# 02_MCU.net
KiCad netlist of a schematic drawn in Altium Designer
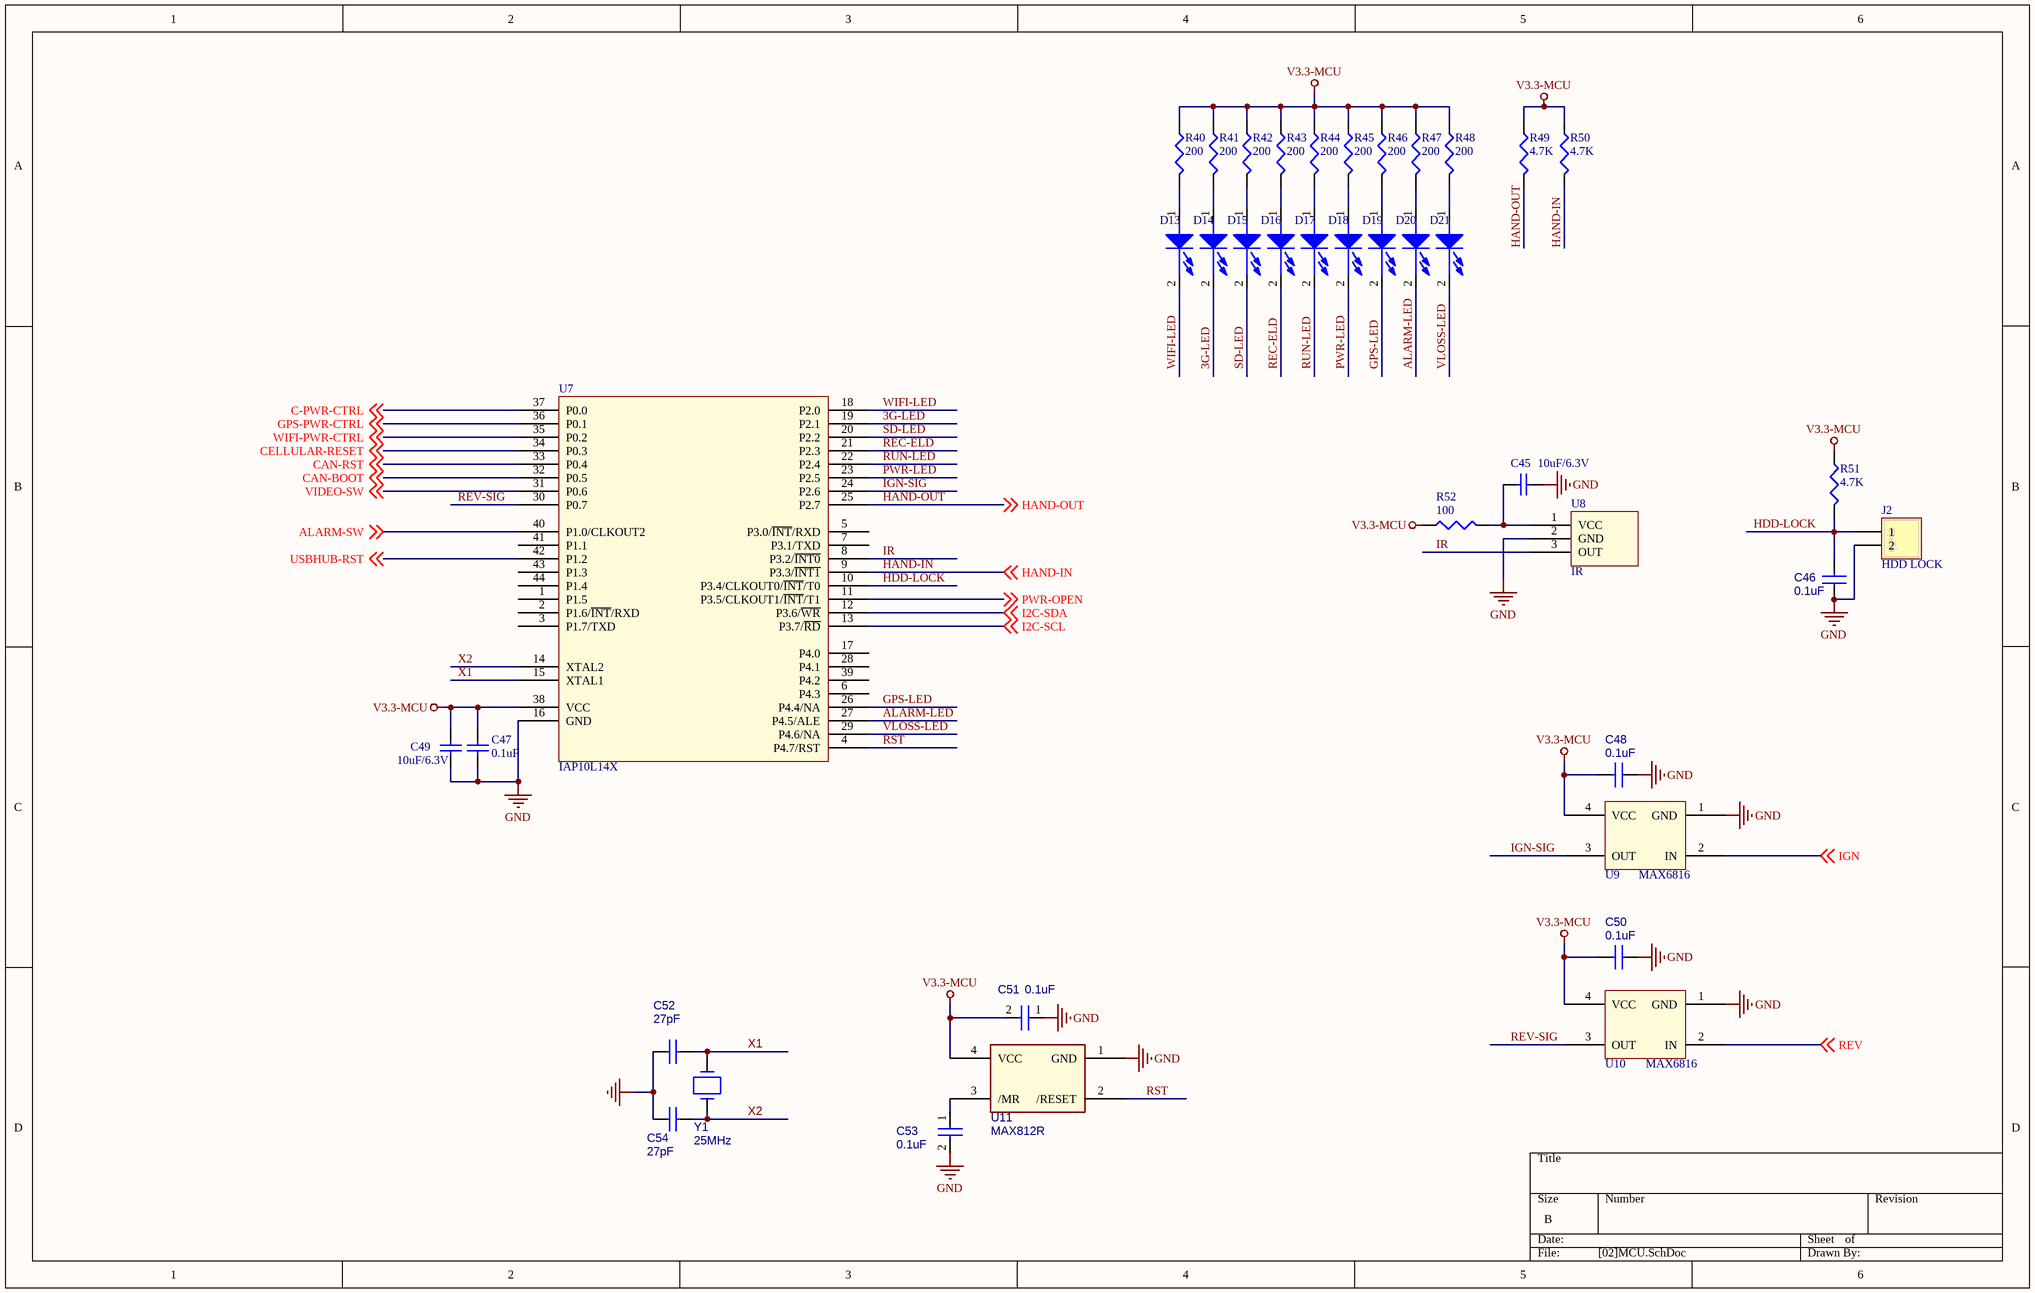
[diagram p0: [02]MCU.SchDoc]

(export (version "E")
  (design (tool "Eeschema 10.0.6"))
  (components
    (comp (ref "C45")
      (value "10uF/6.3V")
      (footprint "0805")
      (description "Capacitor")
      (libsource (lib "Miscellaneous Devices") (part "Cap"))
    )
    (comp (ref "C46") (value "0.1uF") (libsource (lib "*") (part "CAP")))
    (comp (ref "C47")
      (value "0.1uF")
      (footprint "0603")
      (description "Capacitor")
      (libsource (lib "Miscellaneous Devices") (part "Cap"))
    )
    (comp (ref "C48") (value "0.1uF") (libsource (lib "*") (part "CAP")))
    (comp (ref "C49")
      (value "10uF/6.3V")
      (footprint "0805")
      (description "Capacitor")
      (libsource (lib "Miscellaneous Devices") (part "Cap"))
    )
    (comp (ref "C50") (value "0.1uF") (libsource (lib "*") (part "CAP")))
    (comp (ref "C51") (value "0.1uF") (libsource (lib "*") (part "CAP NP_Dup2")))
    (comp (ref "C52") (value "27pF") (libsource (lib "*") (part "CAP_Dup1")))
    (comp (ref "C53") (value "0.1uF") (libsource (lib "*") (part "CAP NP_Dup2")))
    (comp (ref "C54") (value "27pF") (libsource (lib "*") (part "CAP_Dup1")))
    (comp (ref "D13") (value "LED GREEN") (footprint "LED-3MM") (libsource (lib "*") (part "LN01401_1")))
    (comp (ref "D14") (value "LED GREEN") (footprint "LED-3MM") (libsource (lib "*") (part "LN01401_1")))
    (comp (ref "D15") (value "LED GREEN") (footprint "LED-3MM") (libsource (lib "*") (part "LN01401_1")))
    (comp (ref "D16") (value "LED GREEN") (footprint "LED-3MM") (libsource (lib "*") (part "LN01401_1")))
    (comp (ref "D17") (value "LED GREEN") (footprint "LED-3MM") (libsource (lib "*") (part "LN01401_1")))
    (comp (ref "D18") (value "LED GREEN") (footprint "LED-3MM") (libsource (lib "*") (part "LN01401_1")))
    (comp (ref "D19") (value "LED GREEN") (footprint "LED-3MM") (libsource (lib "*") (part "LN01401_1")))
    (comp (ref "D20") (value "LED GREEN") (footprint "LED-3MM") (libsource (lib "*") (part "LN01401_1")))
    (comp (ref "D21") (value "LED GREEN") (footprint "LED-3MM") (libsource (lib "*") (part "LN01401_1")))
    (comp (ref "J2")
      (value "HDD LOCK")
      (footprint "CON-2PIN")
      (description "Header, 2-Pin")
      (fields (field (name "PUBLISHER") "Altium Limited"))
      (libsource (lib "Miscellaneous Connectors") (part "Header 2"))
    )
    (comp (ref "R40") (value "200") (footprint "0603") (libsource (lib "*") (part "CR16-1003FM")))
    (comp (ref "R41") (value "200") (footprint "0603") (libsource (lib "*") (part "CR16-1003FM")))
    (comp (ref "R42") (value "200") (footprint "0603") (libsource (lib "*") (part "CR16-1003FM")))
    (comp (ref "R43") (value "200") (footprint "0603") (libsource (lib "*") (part "CR16-1003FM")))
    (comp (ref "R44") (value "200") (footprint "0603") (libsource (lib "*") (part "CR16-1003FM")))
    (comp (ref "R45") (value "200") (footprint "0603") (libsource (lib "*") (part "CR16-1003FM")))
    (comp (ref "R46") (value "200") (footprint "0603") (libsource (lib "*") (part "CR16-1003FM")))
    (comp (ref "R47") (value "200") (footprint "0603") (libsource (lib "*") (part "CR16-1003FM")))
    (comp (ref "R48") (value "200") (footprint "0603") (libsource (lib "*") (part "CR16-1003FM")))
    (comp (ref "R49") (value "4.7K") (footprint "0603") (libsource (lib "*") (part "CR16-1003FM")))
    (comp (ref "R50") (value "4.7K") (footprint "0603") (libsource (lib "*") (part "CR16-1003FM")))
    (comp (ref "R51") (value "4.7K") (footprint "0603") (libsource (lib "*") (part "CR16-1003FM")))
    (comp (ref "R52") (value "100") (footprint "0603") (libsource (lib "*") (part "CR16-1003FM")))
    (comp (ref "U7") (value "IAP10L14X") (footprint "LQFP44") (libsource (lib "Schlib") (part "IAP10L14X")))
    (comp (ref "U8") (value "IR") (footprint "IR") (libsource (lib "Schlib") (part "IR")))
    (comp (ref "U9") (value "MAX6816") (footprint "SOT143") (libsource (lib "Schlib") (part "MAX6816")))
    (comp (ref "U10") (value "MAX6816") (footprint "SOT143") (libsource (lib "Schlib") (part "MAX6816")))
    (comp (ref "U11") (value "MAX812R") (libsource (lib "*") (part "MAX811")))
    (comp (ref "Y1") (value "25MHz") (libsource (lib "*") (part "CRYSTAL")))
  )
  (nets
    (net (code "1") (name "/3G-LED") (class "Default")
      (node (ref "D14") (pin "2") (pinfunction "CATHODE_2") (pintype "passive"))
      (node (ref "U7") (pin "19") (pinfunction "P2.1_19") (pintype "passive"))
    )
    (net (code "2") (name "/ALARM-LED") (class "Default")
      (node (ref "D20") (pin "2") (pinfunction "CATHODE_2") (pintype "passive"))
      (node (ref "U7") (pin "27") (pinfunction "P4.5/ALE_27") (pintype "passive"))
    )
    (net (code "3") (name "/GPS-LED") (class "Default")
      (node (ref "D19") (pin "2") (pinfunction "CATHODE_2") (pintype "passive"))
      (node (ref "U7") (pin "26") (pinfunction "P4.4/NA_26") (pintype "passive"))
    )
    (net (code "4") (name "/HDD-LOCK") (class "Default")
      (node (ref "C46") (pin "2") (pinfunction "2_2") (pintype "passive"))
      (node (ref "J2") (pin "1") (pinfunction "1_1") (pintype "passive"))
      (node (ref "R51") (pin "2") (pinfunction "2_2") (pintype "passive"))
      (node (ref "U7") (pin "10") (pinfunction "P3.4/CLKOUT0/~{INT}/T0_10") (pintype "passive"))
    )
    (net (code "5") (name "/IGN-SIG") (class "Default")
      (node (ref "U7") (pin "24") (pinfunction "P2.6_24") (pintype "passive"))
      (node (ref "U9") (pin "3") (pinfunction "OUT_3") (pintype "passive"))
    )
    (net (code "6") (name "/IR") (class "Default")
      (node (ref "U7") (pin "8") (pinfunction "P3.2/~{INT0}_8") (pintype "passive"))
      (node (ref "U8") (pin "3") (pinfunction "OUT_3") (pintype "passive"))
    )
    (net (code "7") (name "/PWR-LED") (class "Default")
      (node (ref "D18") (pin "2") (pinfunction "CATHODE_2") (pintype "passive"))
      (node (ref "U7") (pin "23") (pinfunction "P2.5_23") (pintype "passive"))
    )
    (net (code "8") (name "/REC-ELD") (class "Default")
      (node (ref "D16") (pin "2") (pinfunction "CATHODE_2") (pintype "passive"))
      (node (ref "U7") (pin "21") (pinfunction "P2.3_21") (pintype "passive"))
    )
    (net (code "9") (name "/REV-SIG") (class "Default")
      (node (ref "U10") (pin "3") (pinfunction "OUT_3") (pintype "passive"))
      (node (ref "U7") (pin "30") (pinfunction "P0.7_30") (pintype "passive"))
    )
    (net (code "10") (name "/RST") (class "Default")
      (node (ref "U11") (pin "2") (pinfunction "/RESET_2") (pintype "passive"))
      (node (ref "U7") (pin "4") (pinfunction "P4.7/RST_4") (pintype "passive"))
    )
    (net (code "11") (name "/RUN-LED") (class "Default")
      (node (ref "D17") (pin "2") (pinfunction "CATHODE_2") (pintype "passive"))
      (node (ref "U7") (pin "22") (pinfunction "P2.4_22") (pintype "passive"))
    )
    (net (code "12") (name "/SD-LED") (class "Default")
      (node (ref "D15") (pin "2") (pinfunction "CATHODE_2") (pintype "passive"))
      (node (ref "U7") (pin "20") (pinfunction "P2.2_20") (pintype "passive"))
    )
    (net (code "13") (name "/VLOSS-LED") (class "Default")
      (node (ref "D21") (pin "2") (pinfunction "CATHODE_2") (pintype "passive"))
      (node (ref "U7") (pin "29") (pinfunction "P4.6/NA_29") (pintype "passive"))
    )
    (net (code "14") (name "/WIFI-LED") (class "Default")
      (node (ref "D13") (pin "2") (pinfunction "CATHODE_2") (pintype "passive"))
      (node (ref "U7") (pin "18") (pinfunction "P2.0_18") (pintype "passive"))
    )
    (net (code "15") (name "/X1") (class "Default")
      (node (ref "C52") (pin "2") (pinfunction "2_2") (pintype "passive"))
      (node (ref "U7") (pin "15") (pinfunction "XTAL1_15") (pintype "passive"))
      (node (ref "Y1") (pin "2") (pinfunction "2_2") (pintype "passive"))
    )
    (net (code "16") (name "/X2") (class "Default")
      (node (ref "C54") (pin "2") (pinfunction "2_2") (pintype "passive"))
      (node (ref "U7") (pin "14") (pinfunction "XTAL2_14") (pintype "passive"))
      (node (ref "Y1") (pin "1") (pinfunction "1_1") (pintype "passive"))
    )
    (net (code "17") (name "ALARM-SW") (class "Default")
      (node (ref "U7") (pin "40") (pinfunction "P1.0/CLKOUT2_40") (pintype "passive"))
    )
    (net (code "18") (name "C-PWR-CTRL") (class "Default")
      (node (ref "U7") (pin "37") (pinfunction "P0.0_37") (pintype "passive"))
    )
    (net (code "19") (name "CAN-BOOT") (class "Default")
      (node (ref "U7") (pin "32") (pinfunction "P0.5_32") (pintype "passive"))
    )
    (net (code "20") (name "CAN-RST") (class "Default")
      (node (ref "U7") (pin "33") (pinfunction "P0.4_33") (pintype "passive"))
    )
    (net (code "21") (name "CELLULAR-RESET") (class "Default")
      (node (ref "U7") (pin "34") (pinfunction "P0.3_34") (pintype "passive"))
    )
    (net (code "22") (name "GND") (class "Default")
      (node (ref "C45") (pin "1") (pinfunction "1_1") (pintype "passive"))
      (node (ref "C46") (pin "1") (pinfunction "1_1") (pintype "passive"))
      (node (ref "C47") (pin "1") (pinfunction "1_1") (pintype "passive"))
      (node (ref "C48") (pin "1") (pinfunction "1_1") (pintype "passive"))
      (node (ref "C49") (pin "1") (pinfunction "1_1") (pintype "passive"))
      (node (ref "C50") (pin "1") (pinfunction "1_1") (pintype "passive"))
      (node (ref "C51") (pin "1") (pinfunction "1_1") (pintype "passive"))
      (node (ref "C52") (pin "1") (pinfunction "1_1") (pintype "passive"))
      (node (ref "C53") (pin "2") (pinfunction "2_2") (pintype "passive"))
      (node (ref "C54") (pin "1") (pinfunction "1_1") (pintype "passive"))
      (node (ref "J2") (pin "2") (pinfunction "2_2") (pintype "passive"))
      (node (ref "U10") (pin "1") (pinfunction "GND_1") (pintype "passive"))
      (node (ref "U11") (pin "1") (pinfunction "GND_1") (pintype "passive"))
      (node (ref "U7") (pin "16") (pinfunction "GND_16") (pintype "passive"))
      (node (ref "U8") (pin "2") (pinfunction "GND_2") (pintype "passive"))
      (node (ref "U9") (pin "1") (pinfunction "GND_1") (pintype "passive"))
    )
    (net (code "23") (name "GPS-PWR-CTRL") (class "Default")
      (node (ref "U7") (pin "36") (pinfunction "P0.1_36") (pintype "passive"))
    )
    (net (code "24") (name "HAND-IN") (class "Default")
      (node (ref "R50") (pin "2") (pinfunction "2_2") (pintype "passive"))
      (node (ref "U7") (pin "9") (pinfunction "P3.3/~{INT1}_9") (pintype "passive"))
    )
    (net (code "25") (name "HAND-OUT") (class "Default")
      (node (ref "R49") (pin "2") (pinfunction "2_2") (pintype "passive"))
      (node (ref "U7") (pin "25") (pinfunction "P2.7_25") (pintype "passive"))
    )
    (net (code "26") (name "I2C-SCL") (class "Default")
      (node (ref "U7") (pin "13") (pinfunction "P3.7/~{RD}_13") (pintype "passive"))
    )
    (net (code "27") (name "I2C-SDA") (class "Default")
      (node (ref "U7") (pin "12") (pinfunction "P3.6/~{WR}_12") (pintype "passive"))
    )
    (net (code "28") (name "IGN") (class "Default")
      (node (ref "U9") (pin "2") (pinfunction "IN_2") (pintype "passive"))
    )
    (net (code "29") (name "Net-(D13-ANODE)") (class "Default")
      (node (ref "D13") (pin "1") (pinfunction "ANODE_1") (pintype "passive"))
      (node (ref "R40") (pin "2") (pinfunction "2_2") (pintype "passive"))
    )
    (net (code "30") (name "Net-(D14-ANODE)") (class "Default")
      (node (ref "D14") (pin "1") (pinfunction "ANODE_1") (pintype "passive"))
      (node (ref "R41") (pin "2") (pinfunction "2_2") (pintype "passive"))
    )
    (net (code "31") (name "Net-(D15-ANODE)") (class "Default")
      (node (ref "D15") (pin "1") (pinfunction "ANODE_1") (pintype "passive"))
      (node (ref "R42") (pin "2") (pinfunction "2_2") (pintype "passive"))
    )
    (net (code "32") (name "Net-(D16-ANODE)") (class "Default")
      (node (ref "D16") (pin "1") (pinfunction "ANODE_1") (pintype "passive"))
      (node (ref "R43") (pin "2") (pinfunction "2_2") (pintype "passive"))
    )
    (net (code "33") (name "Net-(D17-ANODE)") (class "Default")
      (node (ref "D17") (pin "1") (pinfunction "ANODE_1") (pintype "passive"))
      (node (ref "R44") (pin "2") (pinfunction "2_2") (pintype "passive"))
    )
    (net (code "34") (name "Net-(D18-ANODE)") (class "Default")
      (node (ref "D18") (pin "1") (pinfunction "ANODE_1") (pintype "passive"))
      (node (ref "R45") (pin "2") (pinfunction "2_2") (pintype "passive"))
    )
    (net (code "35") (name "Net-(D19-ANODE)") (class "Default")
      (node (ref "D19") (pin "1") (pinfunction "ANODE_1") (pintype "passive"))
      (node (ref "R46") (pin "2") (pinfunction "2_2") (pintype "passive"))
    )
    (net (code "36") (name "Net-(D20-ANODE)") (class "Default")
      (node (ref "D20") (pin "1") (pinfunction "ANODE_1") (pintype "passive"))
      (node (ref "R47") (pin "2") (pinfunction "2_2") (pintype "passive"))
    )
    (net (code "37") (name "Net-(D21-ANODE)") (class "Default")
      (node (ref "D21") (pin "1") (pinfunction "ANODE_1") (pintype "passive"))
      (node (ref "R48") (pin "2") (pinfunction "2_2") (pintype "passive"))
    )
    (net (code "38") (name "Net-(U8-VCC)") (class "Default")
      (node (ref "C45") (pin "2") (pinfunction "2_2") (pintype "passive"))
      (node (ref "R52") (pin "2") (pinfunction "2_2") (pintype "passive"))
      (node (ref "U8") (pin "1") (pinfunction "VCC_1") (pintype "passive"))
    )
    (net (code "39") (name "Net-(U11-{slash}MR)") (class "Default")
      (node (ref "C53") (pin "1") (pinfunction "1_1") (pintype "passive"))
      (node (ref "U11") (pin "3") (pinfunction "/MR_3") (pintype "passive"))
    )
    (net (code "40") (name "PWR-OPEN") (class "Default")
      (node (ref "U7") (pin "11") (pinfunction "P3.5/CLKOUT1/~{INT}/T1_11") (pintype "passive"))
    )
    (net (code "41") (name "REV") (class "Default")
      (node (ref "U10") (pin "2") (pinfunction "IN_2") (pintype "passive"))
    )
    (net (code "42") (name "USBHUB-RST") (class "Default")
      (node (ref "U7") (pin "42") (pinfunction "P1.2_42") (pintype "passive"))
    )
    (net (code "43") (name "V3.3-MCU") (class "Default")
      (node (ref "C47") (pin "2") (pinfunction "2_2") (pintype "passive"))
      (node (ref "C48") (pin "2") (pinfunction "2_2") (pintype "passive"))
      (node (ref "C49") (pin "2") (pinfunction "2_2") (pintype "passive"))
      (node (ref "C50") (pin "2") (pinfunction "2_2") (pintype "passive"))
      (node (ref "C51") (pin "2") (pinfunction "2_2") (pintype "passive"))
      (node (ref "R40") (pin "1") (pinfunction "1_1") (pintype "passive"))
      (node (ref "R41") (pin "1") (pinfunction "1_1") (pintype "passive"))
      (node (ref "R42") (pin "1") (pinfunction "1_1") (pintype "passive"))
      (node (ref "R43") (pin "1") (pinfunction "1_1") (pintype "passive"))
      (node (ref "R44") (pin "1") (pinfunction "1_1") (pintype "passive"))
      (node (ref "R45") (pin "1") (pinfunction "1_1") (pintype "passive"))
      (node (ref "R46") (pin "1") (pinfunction "1_1") (pintype "passive"))
      (node (ref "R47") (pin "1") (pinfunction "1_1") (pintype "passive"))
      (node (ref "R48") (pin "1") (pinfunction "1_1") (pintype "passive"))
      (node (ref "R49") (pin "1") (pinfunction "1_1") (pintype "passive"))
      (node (ref "R50") (pin "1") (pinfunction "1_1") (pintype "passive"))
      (node (ref "R51") (pin "1") (pinfunction "1_1") (pintype "passive"))
      (node (ref "R52") (pin "1") (pinfunction "1_1") (pintype "passive"))
      (node (ref "U10") (pin "4") (pinfunction "VCC_4") (pintype "passive"))
      (node (ref "U11") (pin "4") (pinfunction "VCC_4") (pintype "passive"))
      (node (ref "U7") (pin "38") (pinfunction "VCC_38") (pintype "passive"))
      (node (ref "U9") (pin "4") (pinfunction "VCC_4") (pintype "passive"))
    )
    (net (code "44") (name "VIDEO-SW") (class "Default")
      (node (ref "U7") (pin "31") (pinfunction "P0.6_31") (pintype "passive"))
    )
    (net (code "45") (name "WIFI-PWR-CTRL") (class "Default")
      (node (ref "U7") (pin "35") (pinfunction "P0.2_35") (pintype "passive"))
    )
    (net (code "46") (name "unconnected-(U7-P1.1-Pad41)") (class "Default")
      (node (ref "U7") (pin "41") (pinfunction "P1.1_41") (pintype "passive"))
    )
    (net (code "47") (name "unconnected-(U7-P1.3-Pad43)") (class "Default")
      (node (ref "U7") (pin "43") (pinfunction "P1.3_43") (pintype "passive"))
    )
    (net (code "48") (name "unconnected-(U7-P1.4-Pad44)") (class "Default")
      (node (ref "U7") (pin "44") (pinfunction "P1.4_44") (pintype "passive"))
    )
    (net (code "49") (name "unconnected-(U7-P1.5-Pad1)") (class "Default")
      (node (ref "U7") (pin "1") (pinfunction "P1.5_1") (pintype "passive"))
    )
    (net (code "50") (name "unconnected-(U7-P1.6{slash}~{INT}{slash}RXD-Pad2)") (class "Default")
      (node (ref "U7") (pin "2") (pinfunction "P1.6/~{INT}/RXD_2") (pintype "passive"))
    )
    (net (code "51") (name "unconnected-(U7-P1.7{slash}TXD-Pad3)") (class "Default")
      (node (ref "U7") (pin "3") (pinfunction "P1.7/TXD_3") (pintype "passive"))
    )
    (net (code "52") (name "unconnected-(U7-P3.0{slash}~{INT}{slash}RXD-Pad5)") (class "Default")
      (node (ref "U7") (pin "5") (pinfunction "P3.0/~{INT}/RXD_5") (pintype "passive"))
    )
    (net (code "53") (name "unconnected-(U7-P3.1{slash}TXD-Pad7)") (class "Default")
      (node (ref "U7") (pin "7") (pinfunction "P3.1/TXD_7") (pintype "passive"))
    )
    (net (code "54") (name "unconnected-(U7-P4.0-Pad17)") (class "Default")
      (node (ref "U7") (pin "17") (pinfunction "P4.0_17") (pintype "passive"))
    )
    (net (code "55") (name "unconnected-(U7-P4.1-Pad28)") (class "Default")
      (node (ref "U7") (pin "28") (pinfunction "P4.1_28") (pintype "passive"))
    )
    (net (code "56") (name "unconnected-(U7-P4.2-Pad39)") (class "Default")
      (node (ref "U7") (pin "39") (pinfunction "P4.2_39") (pintype "passive"))
    )
    (net (code "57") (name "unconnected-(U7-P4.3-Pad6)") (class "Default")
      (node (ref "U7") (pin "6") (pinfunction "P4.3_6") (pintype "passive"))
    )
  )
)
